# LV_Schematic.net
KiCad netlist of a schematic drawn in Altium Designer
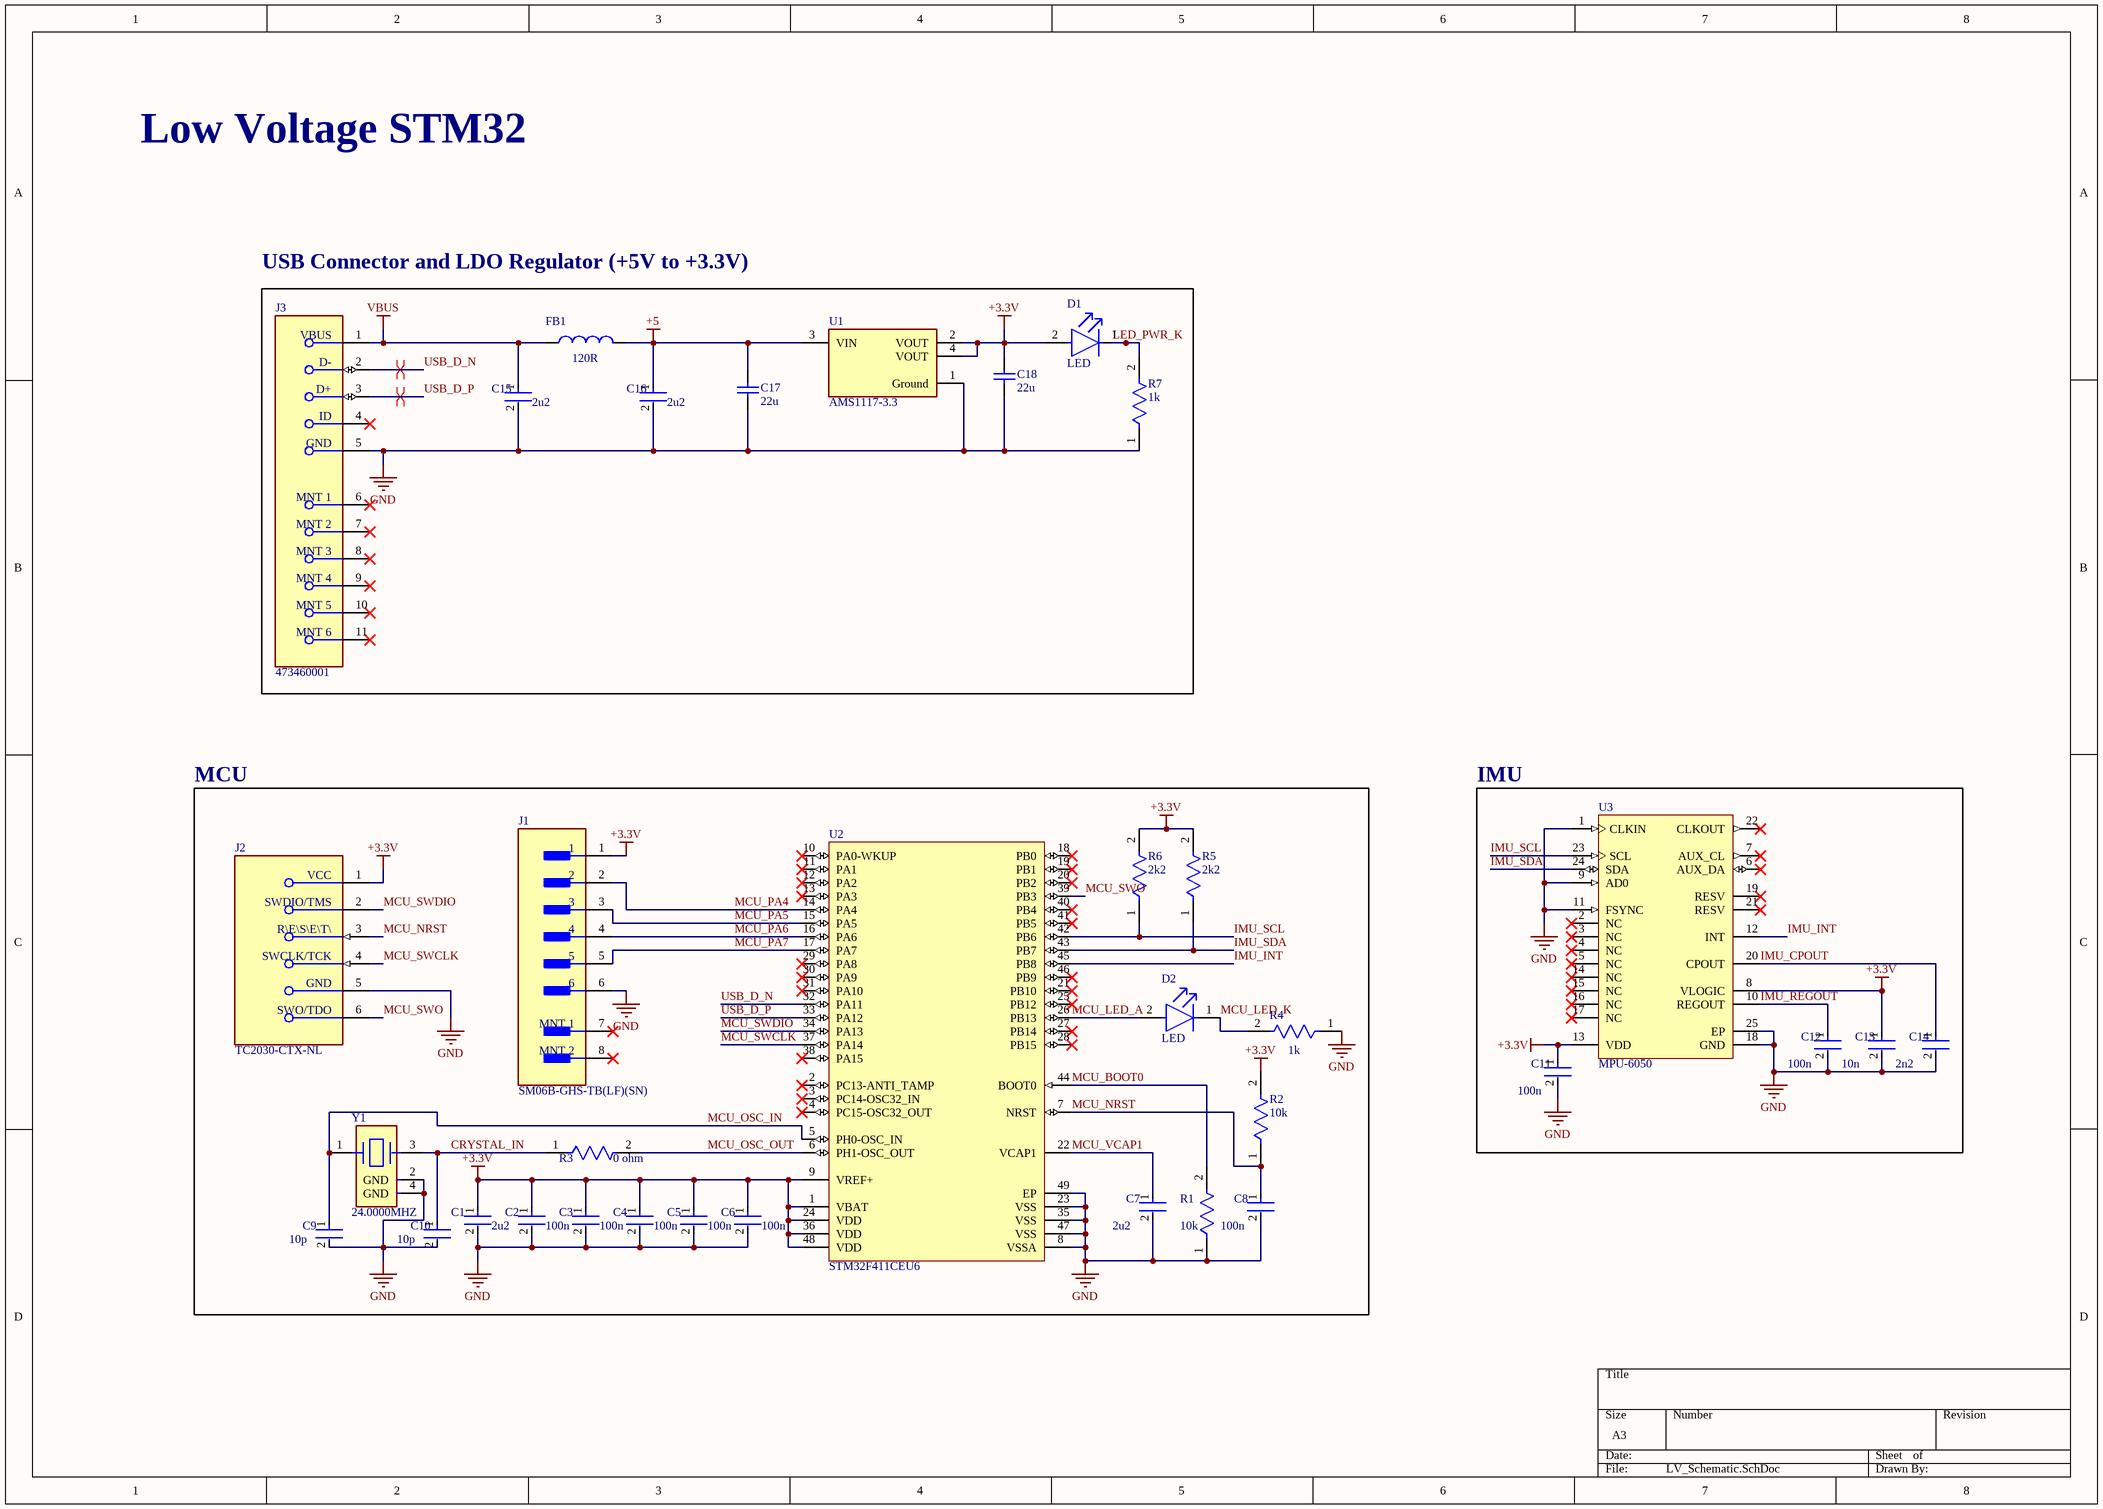
[diagram p0: LV_Schematic.SchDoc]

(export (version "E")
  (design (tool "Eeschema 10.0.6"))
  (components
    (comp (ref "C1")
      (value "2u2")
      (footprint "FP-0603-L_1_6_0_15-W_0_8-IPC_A")
      (description "None")
      (fields (field (name "TOLERANCE") "10%"))
      (libsource (lib "Altium Content Vault") (part "11868f565c42a9108669ba33697ecf6"))
    )
    (comp (ref "C2")
      (value "100n")
      (footprint "FP-CC0402-MFG")
      (description "CAP CER 0.1UF 16V X5R 0402")
      (fields
        (field (name "OCTOPART") "https://octopart.com/cc0402mrx5r7bb104-yageo-33242280")
        (field (name "MANUFACTURER PART NUMBER") "CC0402MRX5R7BB104")
      )
      (libsource (lib "Altium Content Vault") (part "11868f565c42a9108669ba33697ecf6"))
    )
    (comp (ref "C3")
      (value "100n")
      (footprint "FP-CC0402-MFG")
      (description "CAP CER 0.1UF 16V X5R 0402")
      (fields
        (field (name "OCTOPART") "https://octopart.com/cc0402mrx5r7bb104-yageo-33242280")
        (field (name "MANUFACTURER PART NUMBER") "CC0402MRX5R7BB104")
      )
      (libsource (lib "Altium Content Vault") (part "11868f565c42a9108669ba33697ecf6"))
    )
    (comp (ref "C4")
      (value "100n")
      (footprint "FP-CC0402-MFG")
      (description "CAP CER 0.1UF 16V X5R 0402")
      (fields
        (field (name "OCTOPART") "https://octopart.com/cc0402mrx5r7bb104-yageo-33242280")
        (field (name "MANUFACTURER PART NUMBER") "CC0402MRX5R7BB104")
      )
      (libsource (lib "Altium Content Vault") (part "11868f565c42a9108669ba33697ecf6"))
    )
    (comp (ref "C5")
      (value "100n")
      (footprint "FP-CC0402-MFG")
      (description "CAP CER 0.1UF 16V X5R 0402")
      (fields
        (field (name "OCTOPART") "https://octopart.com/cc0402mrx5r7bb104-yageo-33242280")
        (field (name "MANUFACTURER PART NUMBER") "CC0402MRX5R7BB104")
      )
      (libsource (lib "Altium Content Vault") (part "11868f565c42a9108669ba33697ecf6"))
    )
    (comp (ref "C6")
      (value "100n")
      (footprint "FP-CC0402-MFG")
      (description "CAP CER 0.1UF 16V X5R 0402")
      (fields
        (field (name "OCTOPART") "https://octopart.com/cc0402mrx5r7bb104-yageo-33242280")
        (field (name "MANUFACTURER PART NUMBER") "CC0402MRX5R7BB104")
      )
      (libsource (lib "Altium Content Vault") (part "11868f565c42a9108669ba33697ecf6"))
    )
    (comp (ref "C7")
      (value "2u2")
      (footprint "FP-0603-L_1_6_0_15-W_0_8-IPC_A")
      (description "None")
      (fields (field (name "TOLERANCE") "10%"))
      (libsource (lib "Altium Content Vault") (part "11868f565c42a9108669ba33697ecf6"))
    )
    (comp (ref "C8")
      (value "100n")
      (footprint "FP-CC0402-MFG")
      (description "CAP CER 0.1UF 16V X5R 0402")
      (fields
        (field (name "OCTOPART") "https://octopart.com/cc0402mrx5r7bb104-yageo-33242280")
        (field (name "MANUFACTURER PART NUMBER") "CC0402MRX5R7BB104")
      )
      (libsource (lib "Altium Content Vault") (part "11868f565c42a9108669ba33697ecf6"))
    )
    (comp (ref "C9")
      (value "10p")
      (footprint "FP-CC0402-MFG")
      (description "CAP CER 0.1UF 16V X5R 0402")
      (fields
        (field (name "OCTOPART") "https://octopart.com/cc0402mrx5r7bb104-yageo-33242280")
        (field (name "MANUFACTURER PART NUMBER") "CC0402MRX5R7BB104")
      )
      (libsource (lib "Altium Content Vault") (part "11868f565c42a9108669ba33697ecf6"))
    )
    (comp (ref "C10")
      (value "10p")
      (footprint "FP-CC0402-MFG")
      (description "CAP CER 0.1UF 16V X5R 0402")
      (fields
        (field (name "OCTOPART") "https://octopart.com/cc0402mrx5r7bb104-yageo-33242280")
        (field (name "MANUFACTURER PART NUMBER") "CC0402MRX5R7BB104")
      )
      (libsource (lib "Altium Content Vault") (part "11868f565c42a9108669ba33697ecf6"))
    )
    (comp (ref "C11")
      (value "100n")
      (footprint "FP-CC0402-MFG")
      (description "CAP CER 0.1UF 16V X5R 0402")
      (fields
        (field (name "OCTOPART") "https://octopart.com/cc0402mrx5r7bb104-yageo-33242280")
        (field (name "MANUFACTURER PART NUMBER") "CC0402MRX5R7BB104")
      )
      (libsource (lib "Altium Content Vault") (part "11868f565c42a9108669ba33697ecf6"))
    )
    (comp (ref "C12")
      (value "100n")
      (footprint "FP-CC0402-MFG")
      (description "CAP CER 0.1UF 16V X5R 0402")
      (fields
        (field (name "OCTOPART") "https://octopart.com/cc0402mrx5r7bb104-yageo-33242280")
        (field (name "MANUFACTURER PART NUMBER") "CC0402MRX5R7BB104")
      )
      (libsource (lib "Altium Content Vault") (part "11868f565c42a9108669ba33697ecf6"))
    )
    (comp (ref "C13")
      (value "10n")
      (footprint "FP-CC0402-MFG")
      (description "CAP CER 0.1UF 16V X5R 0402")
      (fields
        (field (name "OCTOPART") "https://octopart.com/cc0402mrx5r7bb104-yageo-33242280")
        (field (name "MANUFACTURER PART NUMBER") "CC0402MRX5R7BB104")
      )
      (libsource (lib "Altium Content Vault") (part "11868f565c42a9108669ba33697ecf6"))
    )
    (comp (ref "C14")
      (value "2n2")
      (footprint "FP-CC0402-MFG")
      (description "CAP CER 0.1UF 16V X5R 0402")
      (fields
        (field (name "OCTOPART") "https://octopart.com/cc0402mrx5r7bb104-yageo-33242280")
        (field (name "MANUFACTURER PART NUMBER") "CC0402MRX5R7BB104")
      )
      (libsource (lib "Altium Content Vault") (part "11868f565c42a9108669ba33697ecf6"))
    )
    (comp (ref "C15")
      (value "2u2")
      (footprint "FP-0603-L_1_6_0_15-W_0_8-IPC_A")
      (description "None")
      (fields (field (name "TOLERANCE") "10%"))
      (libsource (lib "Altium Content Vault") (part "11868f565c42a9108669ba33697ecf6"))
    )
    (comp (ref "C16")
      (value "2u2")
      (footprint "FP-0603-L_1_6_0_15-W_0_8-IPC_A")
      (description "None")
      (fields (field (name "TOLERANCE") "10%"))
      (libsource (lib "Altium Content Vault") (part "11868f565c42a9108669ba33697ecf6"))
    )
    (comp (ref "C17")
      (value "22u")
      (footprint "CAPC2013X152X50ML20T25")
      (fields
        (field (name "MANUFACTURER") "AVX Interconnect / Elco")
        (field (name "PART NUMBER") "0805ZD226MAT2A")
      )
      (libsource (lib "Altium Content Vault") (part "CAP"))
    )
    (comp (ref "C18")
      (value "22u")
      (footprint "CAPC2013X152X50ML20T25")
      (fields
        (field (name "MANUFACTURER") "AVX Interconnect / Elco")
        (field (name "PART NUMBER") "0805ZD226MAT2A")
      )
      (libsource (lib "Altium Content Vault") (part "CAP"))
    )
    (comp (ref "D1")
      (value "LED")
      (footprint "FP-SML-LX0402SOC-TR-MFG")
      (description "LED ORANGE CLEAR SMD")
      (libsource (lib "Altium Content Vault") (part "8706943c75ba83719d021d2fdc84c58"))
    )
    (comp (ref "D2")
      (value "LED")
      (footprint "FP-SML-LX0402SOC-TR-MFG")
      (description "LED ORANGE CLEAR SMD")
      (libsource (lib "Altium Content Vault") (part "8706943c75ba83719d021d2fdc84c58"))
    )
    (comp (ref "FB1")
      (value "120R")
      (footprint "WE-CBF HF_0603_HC")
      (description "Ferrite Bead (emi Suppression), 1.6X0.8X0.8MM (0603), 600O Impedance At 100 Mhz")
      (fields (field (name "TOLERANCE") "25%"))
      (libsource (lib "Altium Content Vault") (part "Ferrite"))
    )
    (comp (ref "J1")
      (value "SM06B-GHS-TB(LF)(SN)")
      (footprint "FP-SM06B-GHS-TB_LF_SN-MFG")
      (description "CONN HEADER SMD R/A 6POS 1.25MM")
      (libsource (lib "Altium Content Vault") (part "ed24c53d9ba001d1a2a686240a95171"))
    )
    (comp (ref "J2")
      (value "TC2030-CTX-NL")
      (footprint "FP-TC2030-CTX-NL-MFG")
      (description "6-Pin “No legs” TC2030 Plug-of-Nails™ Cable for use with ARM Cortex processors")
      (libsource (lib "Altium Content Vault") (part "e3fe093a55dc37473f431e03719485e"))
    )
    (comp (ref "J3")
      (value "473460001")
      (footprint "FP-473460001-MFG")
      (description "CONN RCPT USB2.0 MICRO B SMD R/A")
      (fields
        (field (name "OCTOPART") "https://octopart.com/47346-0001-molex-7164928")
        (field (name "MANUFACTURER") "Molex")
      )
      (libsource (lib "Altium Content Vault") (part "53ae1f1d9b557310b43ca686e5bb76a"))
    )
    (comp (ref "R1")
      (value "10k")
      (footprint "FP-AC0402-MFG")
      (description "RES 11.3kΩ ±0.5% 0.063W 0402")
      (libsource (lib "Altium Content Vault") (part "1029c3af85768c4190bb7ad29bc67b5"))
    )
    (comp (ref "R2")
      (value "10k")
      (footprint "FP-AC0402-MFG")
      (description "RES 11.3kΩ ±0.5% 0.063W 0402")
      (libsource (lib "Altium Content Vault") (part "1029c3af85768c4190bb7ad29bc67b5"))
    )
    (comp (ref "R3")
      (value "0 ohm")
      (footprint "FP-AC0402-MFG")
      (description "RES 11.3kΩ ±0.5% 0.063W 0402")
      (libsource (lib "Altium Content Vault") (part "1029c3af85768c4190bb7ad29bc67b5"))
    )
    (comp (ref "R4")
      (value "1k")
      (footprint "FP-AC0402-MFG")
      (description "RES 11.3kΩ ±0.5% 0.063W 0402")
      (libsource (lib "Altium Content Vault") (part "1029c3af85768c4190bb7ad29bc67b5"))
    )
    (comp (ref "R5")
      (value "2k2")
      (footprint "FP-AC0402-MFG")
      (description "RES 11.3kΩ ±0.5% 0.063W 0402")
      (libsource (lib "Altium Content Vault") (part "1029c3af85768c4190bb7ad29bc67b5"))
    )
    (comp (ref "R6")
      (value "2k2")
      (footprint "FP-AC0402-MFG")
      (description "RES 11.3kΩ ±0.5% 0.063W 0402")
      (libsource (lib "Altium Content Vault") (part "1029c3af85768c4190bb7ad29bc67b5"))
    )
    (comp (ref "R7")
      (value "1k")
      (footprint "FP-AC0402-MFG")
      (description "RES 11.3kΩ ±0.5% 0.063W 0402")
      (libsource (lib "Altium Content Vault") (part "1029c3af85768c4190bb7ad29bc67b5"))
    )
    (comp (ref "U1")
      (value "AMS1117-3.3")
      (footprint "FP-AMS1117-IPC_C")
      (description "LDO Voltage Regulators 1A, 3.3V")
      (fields
        (field (name "OCTOPART") "https://octopart.com/ams1117-3.3-advanced+monolithic+systems-25899300")
        (field (name "MANUFACTURER") "Advanced Monolithic Systems")
      )
      (libsource (lib "Altium Content Vault") (part "8bdbb5f8e77002000e30dd2845d0354"))
    )
    (comp (ref "U2")
      (value "STM32F411CEU6")
      (footprint "STM-UFQFPN48_L")
      (libsource (lib "Altium Content Vault") (part "MC-ARM-STM32F411-UFQFPN48"))
    )
    (comp (ref "U3")
      (value "MPU-6050")
      (footprint "IS-QFN-24_V")
      (fields (field (name "MANUFACTURER") "InvenSense"))
      (libsource (lib "Altium Content Vault") (part "IS-MPU-6050-QFN-24"))
    )
    (comp (ref "Y1")
      (value "24.0000MHZ")
      (footprint "FP-ABM8W-MFG")
      (description "Crystal 24MHz ±10ppm (Tol) ±10ppm (Stability) 7pF FUND 50Ω 4-Pin SMD T/R")
      (libsource (lib "Altium Content Vault") (part "41079aabb0e87794b56622915be14ed"))
    )
  )
  (nets
    (net (code "1") (name "+3.3V") (class "Default")
      (node (ref "C1") (pin "1") (pinfunction "1_1") (pintype "passive"))
      (node (ref "C11") (pin "1") (pinfunction "1_1") (pintype "passive"))
      (node (ref "C13") (pin "1") (pinfunction "1_1") (pintype "passive"))
      (node (ref "C18") (pin "2") (pinfunction "2_2") (pintype "passive"))
      (node (ref "C2") (pin "1") (pinfunction "1_1") (pintype "passive"))
      (node (ref "C3") (pin "1") (pinfunction "1_1") (pintype "passive"))
      (node (ref "C4") (pin "1") (pinfunction "1_1") (pintype "passive"))
      (node (ref "C5") (pin "1") (pinfunction "1_1") (pintype "passive"))
      (node (ref "C6") (pin "1") (pinfunction "1_1") (pintype "passive"))
      (node (ref "D1") (pin "2") (pinfunction "A_2") (pintype "passive"))
      (node (ref "J1") (pin "1") (pinfunction "1_1") (pintype "passive"))
      (node (ref "J2") (pin "1") (pinfunction "VCC_1") (pintype "power_in"))
      (node (ref "R2") (pin "2") (pinfunction "2_2") (pintype "passive"))
      (node (ref "R5") (pin "2") (pinfunction "2_2") (pintype "passive"))
      (node (ref "R6") (pin "2") (pinfunction "2_2") (pintype "passive"))
      (node (ref "U1") (pin "2") (pinfunction "VOUT_2") (pintype "passive"))
      (node (ref "U1") (pin "4") (pinfunction "VOUT_4") (pintype "passive"))
      (node (ref "U2") (pin "1") (pinfunction "VBAT_1") (pintype "power_in"))
      (node (ref "U2") (pin "24") (pinfunction "VDD_24") (pintype "power_in"))
      (node (ref "U2") (pin "36") (pinfunction "VDD_36") (pintype "power_in"))
      (node (ref "U2") (pin "48") (pinfunction "VDD_48") (pintype "power_in"))
      (node (ref "U2") (pin "9") (pinfunction "VREF+_9") (pintype "power_in"))
      (node (ref "U3") (pin "13") (pinfunction "VDD_13") (pintype "power_in"))
      (node (ref "U3") (pin "8") (pinfunction "VLOGIC_8") (pintype "power_in"))
    )
    (net (code "2") (name "+5") (class "Default")
      (node (ref "C16") (pin "1") (pinfunction "1_1") (pintype "passive"))
      (node (ref "C17") (pin "2") (pinfunction "2_2") (pintype "passive"))
      (node (ref "FB1") (pin "2") (pinfunction "2_2") (pintype "passive"))
      (node (ref "U1") (pin "3") (pinfunction "VIN_3") (pintype "power_in"))
    )
    (net (code "3") (name "/CRYSTAL_IN") (class "Default")
      (node (ref "C10") (pin "1") (pinfunction "1_1") (pintype "passive"))
      (node (ref "R3") (pin "1") (pinfunction "1_1") (pintype "passive"))
      (node (ref "Y1") (pin "3") (pinfunction "3_3") (pintype "passive"))
    )
    (net (code "4") (name "/IMU_CPOUT") (class "Default")
      (node (ref "C14") (pin "1") (pinfunction "1_1") (pintype "passive"))
      (node (ref "U3") (pin "20") (pinfunction "CPOUT_20") (pintype "passive"))
    )
    (net (code "5") (name "/IMU_INT") (class "Default")
      (node (ref "U2") (pin "45") (pinfunction "PB8_45") (pintype "bidirectional"))
      (node (ref "U3") (pin "12") (pinfunction "INT_12") (pintype "open_collector"))
    )
    (net (code "6") (name "/IMU_REGOUT") (class "Default")
      (node (ref "C12") (pin "1") (pinfunction "1_1") (pintype "passive"))
      (node (ref "U3") (pin "10") (pinfunction "REGOUT_10") (pintype "passive"))
    )
    (net (code "7") (name "/IMU_SCL") (class "Default")
      (node (ref "R6") (pin "1") (pinfunction "1_1") (pintype "passive"))
      (node (ref "U2") (pin "42") (pinfunction "PB6_42") (pintype "bidirectional"))
      (node (ref "U3") (pin "23") (pinfunction "SCL_23") (pintype "input"))
    )
    (net (code "8") (name "/IMU_SDA") (class "Default")
      (node (ref "R5") (pin "1") (pinfunction "1_1") (pintype "passive"))
      (node (ref "U2") (pin "43") (pinfunction "PB7_43") (pintype "bidirectional"))
      (node (ref "U3") (pin "24") (pinfunction "SDA_24") (pintype "bidirectional"))
    )
    (net (code "9") (name "/LED_PWR_K") (class "Default")
      (node (ref "D1") (pin "1") (pinfunction "C_1") (pintype "passive"))
      (node (ref "R7") (pin "2") (pinfunction "2_2") (pintype "passive"))
    )
    (net (code "10") (name "/MCU_BOOT0") (class "Default")
      (node (ref "R1") (pin "2") (pinfunction "2_2") (pintype "passive"))
      (node (ref "U2") (pin "44") (pinfunction "BOOT0_44") (pintype "input"))
    )
    (net (code "11") (name "/MCU_LED_A") (class "Default")
      (node (ref "D2") (pin "2") (pinfunction "A_2") (pintype "passive"))
      (node (ref "U2") (pin "26") (pinfunction "PB13_26") (pintype "bidirectional"))
    )
    (net (code "12") (name "/MCU_LED_K") (class "Default")
      (node (ref "D2") (pin "1") (pinfunction "C_1") (pintype "passive"))
      (node (ref "R4") (pin "2") (pinfunction "2_2") (pintype "passive"))
    )
    (net (code "13") (name "/MCU_NRST") (class "Default")
      (node (ref "C8") (pin "1") (pinfunction "1_1") (pintype "passive"))
      (node (ref "J2") (pin "3") (pinfunction "~{RESET}_3") (pintype "input"))
      (node (ref "R2") (pin "1") (pinfunction "1_1") (pintype "passive"))
      (node (ref "U2") (pin "7") (pinfunction "NRST_7") (pintype "bidirectional"))
    )
    (net (code "14") (name "/MCU_OSC_IN") (class "Default")
      (node (ref "C9") (pin "1") (pinfunction "1_1") (pintype "passive"))
      (node (ref "U2") (pin "5") (pinfunction "PH0-OSC_IN_5") (pintype "bidirectional"))
      (node (ref "Y1") (pin "1") (pinfunction "1_1") (pintype "passive"))
    )
    (net (code "15") (name "/MCU_OSC_OUT") (class "Default")
      (node (ref "R3") (pin "2") (pinfunction "2_2") (pintype "passive"))
      (node (ref "U2") (pin "6") (pinfunction "PH1-OSC_OUT_6") (pintype "bidirectional"))
    )
    (net (code "16") (name "/MCU_PA4") (class "Default")
      (node (ref "J1") (pin "2") (pinfunction "2_2") (pintype "passive"))
      (node (ref "U2") (pin "14") (pinfunction "PA4_14") (pintype "bidirectional"))
    )
    (net (code "17") (name "/MCU_PA5") (class "Default")
      (node (ref "J1") (pin "3") (pinfunction "3_3") (pintype "passive"))
      (node (ref "U2") (pin "15") (pinfunction "PA5_15") (pintype "bidirectional"))
    )
    (net (code "18") (name "/MCU_PA6") (class "Default")
      (node (ref "J1") (pin "4") (pinfunction "4_4") (pintype "passive"))
      (node (ref "U2") (pin "16") (pinfunction "PA6_16") (pintype "bidirectional"))
    )
    (net (code "19") (name "/MCU_PA7") (class "Default")
      (node (ref "J1") (pin "5") (pinfunction "5_5") (pintype "passive"))
      (node (ref "U2") (pin "17") (pinfunction "PA7_17") (pintype "bidirectional"))
    )
    (net (code "20") (name "/MCU_SWCLK") (class "Default")
      (node (ref "J2") (pin "4") (pinfunction "SWCLK/TCK_4") (pintype "input"))
      (node (ref "U2") (pin "37") (pinfunction "PA14_37") (pintype "bidirectional"))
    )
    (net (code "21") (name "/MCU_SWDIO") (class "Default")
      (node (ref "J2") (pin "2") (pinfunction "SWDIO/TMS_2") (pintype "passive"))
      (node (ref "U2") (pin "34") (pinfunction "PA13_34") (pintype "bidirectional"))
    )
    (net (code "22") (name "/MCU_SWO") (class "Default")
      (node (ref "J2") (pin "6") (pinfunction "SWO/TDO_6") (pintype "passive"))
      (node (ref "U2") (pin "39") (pinfunction "PB3_39") (pintype "bidirectional"))
    )
    (net (code "23") (name "/MCU_VCAP1") (class "Default")
      (node (ref "C7") (pin "1") (pinfunction "1_1") (pintype "passive"))
      (node (ref "U2") (pin "22") (pinfunction "VCAP1_22") (pintype "passive"))
    )
    (net (code "24") (name "/USB_D_N") (class "Default")
      (node (ref "J3") (pin "2") (pinfunction "D-_2") (pintype "bidirectional"))
      (node (ref "U2") (pin "32") (pinfunction "PA11_32") (pintype "bidirectional"))
    )
    (net (code "25") (name "/USB_D_P") (class "Default")
      (node (ref "J3") (pin "3") (pinfunction "D+_3") (pintype "bidirectional"))
      (node (ref "U2") (pin "33") (pinfunction "PA12_33") (pintype "bidirectional"))
    )
    (net (code "26") (name "GND") (class "Default")
      (node (ref "C1") (pin "2") (pinfunction "2_2") (pintype "passive"))
      (node (ref "C10") (pin "2") (pinfunction "2_2") (pintype "passive"))
      (node (ref "C11") (pin "2") (pinfunction "2_2") (pintype "passive"))
      (node (ref "C12") (pin "2") (pinfunction "2_2") (pintype "passive"))
      (node (ref "C13") (pin "2") (pinfunction "2_2") (pintype "passive"))
      (node (ref "C14") (pin "2") (pinfunction "2_2") (pintype "passive"))
      (node (ref "C15") (pin "2") (pinfunction "2_2") (pintype "passive"))
      (node (ref "C16") (pin "2") (pinfunction "2_2") (pintype "passive"))
      (node (ref "C17") (pin "1") (pinfunction "1_1") (pintype "passive"))
      (node (ref "C18") (pin "1") (pinfunction "1_1") (pintype "passive"))
      (node (ref "C2") (pin "2") (pinfunction "2_2") (pintype "passive"))
      (node (ref "C3") (pin "2") (pinfunction "2_2") (pintype "passive"))
      (node (ref "C4") (pin "2") (pinfunction "2_2") (pintype "passive"))
      (node (ref "C5") (pin "2") (pinfunction "2_2") (pintype "passive"))
      (node (ref "C6") (pin "2") (pinfunction "2_2") (pintype "passive"))
      (node (ref "C7") (pin "2") (pinfunction "2_2") (pintype "passive"))
      (node (ref "C8") (pin "2") (pinfunction "2_2") (pintype "passive"))
      (node (ref "C9") (pin "2") (pinfunction "2_2") (pintype "passive"))
      (node (ref "J1") (pin "6") (pinfunction "6_6") (pintype "passive"))
      (node (ref "J2") (pin "5") (pinfunction "GND_5") (pintype "power_in"))
      (node (ref "J3") (pin "5") (pinfunction "GND_5") (pintype "power_in"))
      (node (ref "R1") (pin "1") (pinfunction "1_1") (pintype "passive"))
      (node (ref "R4") (pin "1") (pinfunction "1_1") (pintype "passive"))
      (node (ref "R7") (pin "1") (pinfunction "1_1") (pintype "passive"))
      (node (ref "U1") (pin "1") (pinfunction "Ground_1") (pintype "power_in"))
      (node (ref "U2") (pin "23") (pinfunction "VSS_23") (pintype "power_in"))
      (node (ref "U2") (pin "35") (pinfunction "VSS_35") (pintype "power_in"))
      (node (ref "U2") (pin "47") (pinfunction "VSS_47") (pintype "power_in"))
      (node (ref "U2") (pin "49") (pinfunction "EP_49") (pintype "power_in"))
      (node (ref "U2") (pin "8") (pinfunction "VSSA_8") (pintype "power_in"))
      (node (ref "U3") (pin "1") (pinfunction "CLKIN_1") (pintype "input"))
      (node (ref "U3") (pin "11") (pinfunction "FSYNC_11") (pintype "input"))
      (node (ref "U3") (pin "18") (pinfunction "GND_18") (pintype "power_in"))
      (node (ref "U3") (pin "25") (pinfunction "EP_25") (pintype "power_in"))
      (node (ref "U3") (pin "9") (pinfunction "AD0_9") (pintype "input"))
      (node (ref "Y1") (pin "2") (pinfunction "GND_2") (pintype "power_in"))
      (node (ref "Y1") (pin "4") (pinfunction "GND_4") (pintype "power_in"))
    )
    (net (code "27") (name "VBUS") (class "Default")
      (node (ref "C15") (pin "1") (pinfunction "1_1") (pintype "passive"))
      (node (ref "FB1") (pin "1") (pinfunction "1_1") (pintype "passive"))
      (node (ref "J3") (pin "1") (pinfunction "VBUS_1") (pintype "power_in"))
    )
    (net (code "28") (name "unconnected-(J1-MNT_1-Pad7)") (class "Default")
      (node (ref "J1") (pin "7") (pinfunction "MNT_1_7") (pintype "passive+no_connect"))
    )
    (net (code "29") (name "unconnected-(J1-MNT_2-Pad8)") (class "Default")
      (node (ref "J1") (pin "8") (pinfunction "MNT_2_8") (pintype "passive+no_connect"))
    )
    (net (code "30") (name "unconnected-(J3-ID-Pad4)") (class "Default")
      (node (ref "J3") (pin "4") (pinfunction "ID_4") (pintype "passive+no_connect"))
    )
    (net (code "31") (name "unconnected-(J3-MNT_1-Pad6)") (class "Default")
      (node (ref "J3") (pin "6") (pinfunction "MNT_1_6") (pintype "passive+no_connect"))
    )
    (net (code "32") (name "unconnected-(J3-MNT_2-Pad7)") (class "Default")
      (node (ref "J3") (pin "7") (pinfunction "MNT_2_7") (pintype "passive+no_connect"))
    )
    (net (code "33") (name "unconnected-(J3-MNT_3-Pad8)") (class "Default")
      (node (ref "J3") (pin "8") (pinfunction "MNT_3_8") (pintype "passive+no_connect"))
    )
    (net (code "34") (name "unconnected-(J3-MNT_4-Pad9)") (class "Default")
      (node (ref "J3") (pin "9") (pinfunction "MNT_4_9") (pintype "passive+no_connect"))
    )
    (net (code "35") (name "unconnected-(J3-MNT_5-Pad10)") (class "Default")
      (node (ref "J3") (pin "10") (pinfunction "MNT_5_10") (pintype "passive+no_connect"))
    )
    (net (code "36") (name "unconnected-(J3-MNT_6-Pad11)") (class "Default")
      (node (ref "J3") (pin "11") (pinfunction "MNT_6_11") (pintype "passive+no_connect"))
    )
    (net (code "37") (name "unconnected-(U2-PA0-WKUP-Pad10)") (class "Default")
      (node (ref "U2") (pin "10") (pinfunction "PA0-WKUP_10") (pintype "bidirectional+no_connect"))
    )
    (net (code "38") (name "unconnected-(U2-PA1-Pad11)") (class "Default")
      (node (ref "U2") (pin "11") (pinfunction "PA1_11") (pintype "bidirectional+no_connect"))
    )
    (net (code "39") (name "unconnected-(U2-PA2-Pad12)") (class "Default")
      (node (ref "U2") (pin "12") (pinfunction "PA2_12") (pintype "bidirectional+no_connect"))
    )
    (net (code "40") (name "unconnected-(U2-PA3-Pad13)") (class "Default")
      (node (ref "U2") (pin "13") (pinfunction "PA3_13") (pintype "bidirectional+no_connect"))
    )
    (net (code "41") (name "unconnected-(U2-PA8-Pad29)") (class "Default")
      (node (ref "U2") (pin "29") (pinfunction "PA8_29") (pintype "bidirectional+no_connect"))
    )
    (net (code "42") (name "unconnected-(U2-PA9-Pad30)") (class "Default")
      (node (ref "U2") (pin "30") (pinfunction "PA9_30") (pintype "bidirectional+no_connect"))
    )
    (net (code "43") (name "unconnected-(U2-PA10-Pad31)") (class "Default")
      (node (ref "U2") (pin "31") (pinfunction "PA10_31") (pintype "bidirectional+no_connect"))
    )
    (net (code "44") (name "unconnected-(U2-PA15-Pad38)") (class "Default")
      (node (ref "U2") (pin "38") (pinfunction "PA15_38") (pintype "bidirectional+no_connect"))
    )
    (net (code "45") (name "unconnected-(U2-PB0-Pad18)") (class "Default")
      (node (ref "U2") (pin "18") (pinfunction "PB0_18") (pintype "bidirectional+no_connect"))
    )
    (net (code "46") (name "unconnected-(U2-PB1-Pad19)") (class "Default")
      (node (ref "U2") (pin "19") (pinfunction "PB1_19") (pintype "bidirectional+no_connect"))
    )
    (net (code "47") (name "unconnected-(U2-PB2-Pad20)") (class "Default")
      (node (ref "U2") (pin "20") (pinfunction "PB2_20") (pintype "bidirectional+no_connect"))
    )
    (net (code "48") (name "unconnected-(U2-PB4-Pad40)") (class "Default")
      (node (ref "U2") (pin "40") (pinfunction "PB4_40") (pintype "bidirectional+no_connect"))
    )
    (net (code "49") (name "unconnected-(U2-PB5-Pad41)") (class "Default")
      (node (ref "U2") (pin "41") (pinfunction "PB5_41") (pintype "bidirectional+no_connect"))
    )
    (net (code "50") (name "unconnected-(U2-PB9-Pad46)") (class "Default")
      (node (ref "U2") (pin "46") (pinfunction "PB9_46") (pintype "bidirectional+no_connect"))
    )
    (net (code "51") (name "unconnected-(U2-PB10-Pad21)") (class "Default")
      (node (ref "U2") (pin "21") (pinfunction "PB10_21") (pintype "bidirectional+no_connect"))
    )
    (net (code "52") (name "unconnected-(U2-PB12-Pad25)") (class "Default")
      (node (ref "U2") (pin "25") (pinfunction "PB12_25") (pintype "bidirectional+no_connect"))
    )
    (net (code "53") (name "unconnected-(U2-PB14-Pad27)") (class "Default")
      (node (ref "U2") (pin "27") (pinfunction "PB14_27") (pintype "bidirectional+no_connect"))
    )
    (net (code "54") (name "unconnected-(U2-PB15-Pad28)") (class "Default")
      (node (ref "U2") (pin "28") (pinfunction "PB15_28") (pintype "bidirectional+no_connect"))
    )
    (net (code "55") (name "unconnected-(U2-PC13-ANTI_TAMP-Pad2)") (class "Default")
      (node (ref "U2") (pin "2") (pinfunction "PC13-ANTI_TAMP_2") (pintype "bidirectional+no_connect"))
    )
    (net (code "56") (name "unconnected-(U2-PC14-OSC32_IN-Pad3)") (class "Default")
      (node (ref "U2") (pin "3") (pinfunction "PC14-OSC32_IN_3") (pintype "bidirectional+no_connect"))
    )
    (net (code "57") (name "unconnected-(U2-PC15-OSC32_OUT-Pad4)") (class "Default")
      (node (ref "U2") (pin "4") (pinfunction "PC15-OSC32_OUT_4") (pintype "bidirectional+no_connect"))
    )
    (net (code "58") (name "unconnected-(U3-AUX_CL-Pad7)") (class "Default")
      (node (ref "U3") (pin "7") (pinfunction "AUX_CL_7") (pintype "output+no_connect"))
    )
    (net (code "59") (name "unconnected-(U3-AUX_DA-Pad6)") (class "Default")
      (node (ref "U3") (pin "6") (pinfunction "AUX_DA_6") (pintype "bidirectional+no_connect"))
    )
    (net (code "60") (name "unconnected-(U3-CLKOUT-Pad22)") (class "Default")
      (node (ref "U3") (pin "22") (pinfunction "CLKOUT_22") (pintype "output+no_connect"))
    )
    (net (code "61") (name "unconnected-(U3-NC-Pad2)") (class "Default")
      (node (ref "U3") (pin "2") (pinfunction "NC_2") (pintype "passive+no_connect"))
    )
    (net (code "62") (name "unconnected-(U3-NC-Pad3)") (class "Default")
      (node (ref "U3") (pin "3") (pinfunction "NC_3") (pintype "passive+no_connect"))
    )
    (net (code "63") (name "unconnected-(U3-NC-Pad4)") (class "Default")
      (node (ref "U3") (pin "4") (pinfunction "NC_4") (pintype "passive+no_connect"))
    )
    (net (code "64") (name "unconnected-(U3-NC-Pad5)") (class "Default")
      (node (ref "U3") (pin "5") (pinfunction "NC_5") (pintype "passive+no_connect"))
    )
    (net (code "65") (name "unconnected-(U3-NC-Pad14)") (class "Default")
      (node (ref "U3") (pin "14") (pinfunction "NC_14") (pintype "passive+no_connect"))
    )
    (net (code "66") (name "unconnected-(U3-NC-Pad15)") (class "Default")
      (node (ref "U3") (pin "15") (pinfunction "NC_15") (pintype "passive+no_connect"))
    )
    (net (code "67") (name "unconnected-(U3-NC-Pad16)") (class "Default")
      (node (ref "U3") (pin "16") (pinfunction "NC_16") (pintype "passive+no_connect"))
    )
    (net (code "68") (name "unconnected-(U3-NC-Pad17)") (class "Default")
      (node (ref "U3") (pin "17") (pinfunction "NC_17") (pintype "passive+no_connect"))
    )
    (net (code "69") (name "unconnected-(U3-RESV-Pad19)") (class "Default")
      (node (ref "U3") (pin "19") (pinfunction "RESV_19") (pintype "passive+no_connect"))
    )
    (net (code "70") (name "unconnected-(U3-RESV-Pad21)") (class "Default")
      (node (ref "U3") (pin "21") (pinfunction "RESV_21") (pintype "passive+no_connect"))
    )
  )
)
